# MEMS.net
KiCad netlist of a schematic drawn in Altium Designer
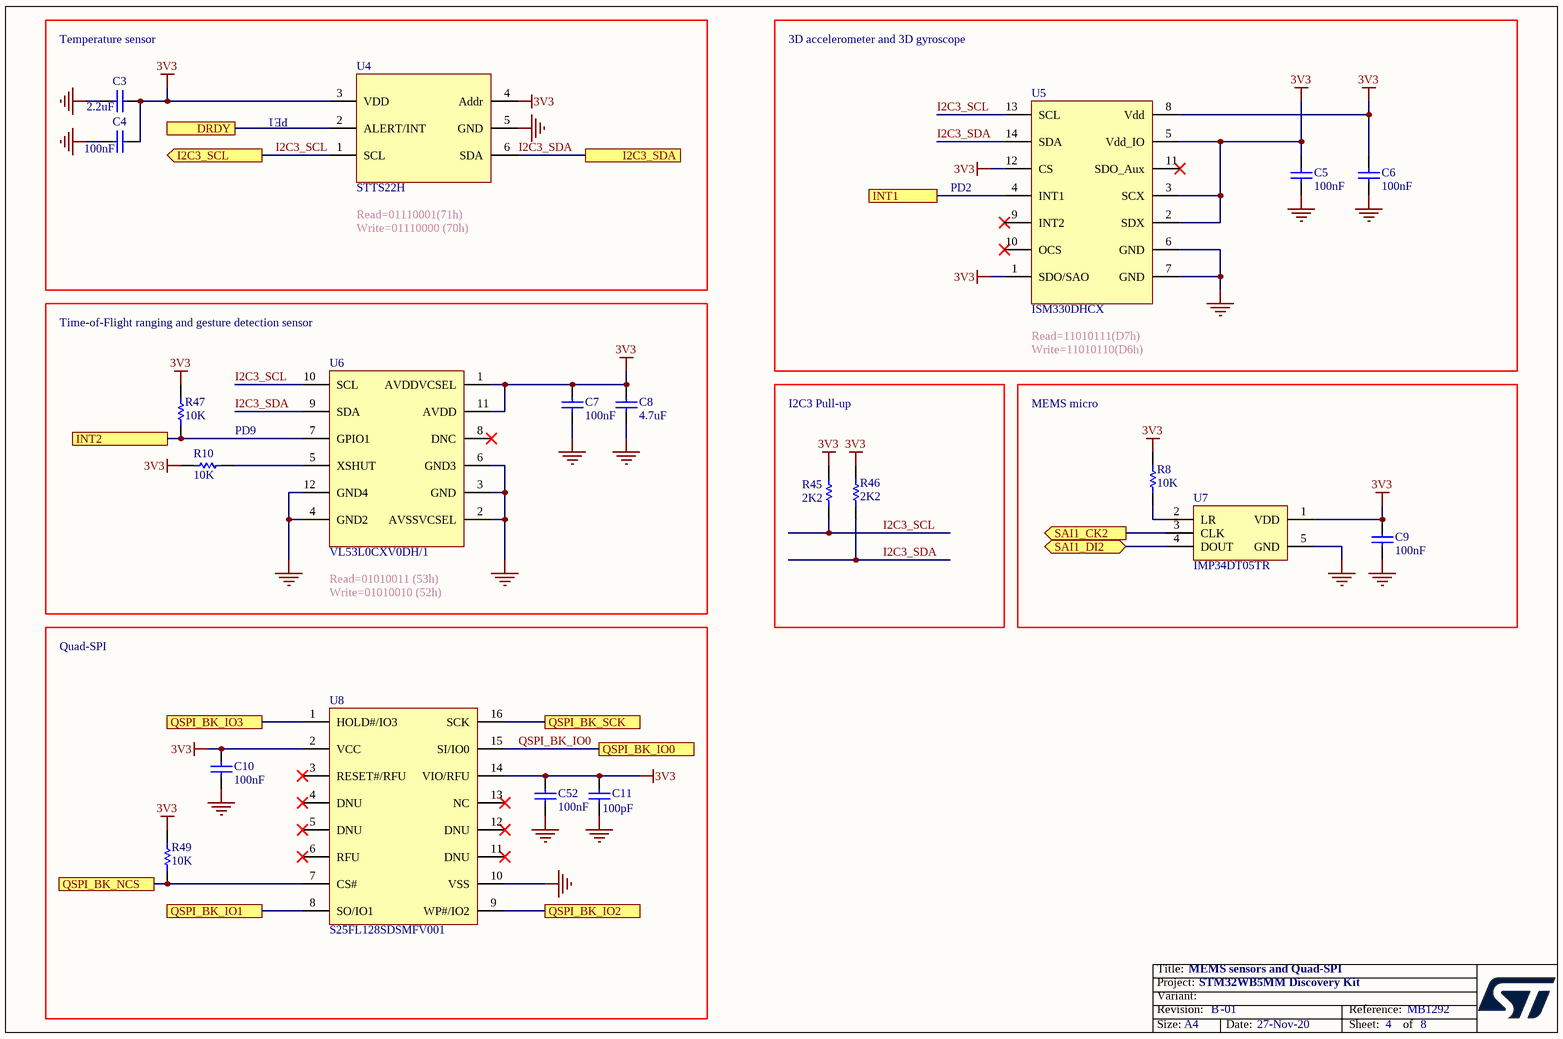
[diagram p0: MEMS.SchDoc]

(export (version "E")
  (design (tool "Eeschema 10.0.6"))
  (components
    (comp (ref "C3")
      (value "2.2uF")
      (footprint "C0603_H0P8")
      (description "Capacitor,MLCC, 2.2uF, 50V, X5R, +/-15%, 0603,T=0.8mm")
      (fields
        (field (name "INTERNAL_PART_NUMBER") "MCD-01540")
        (field (name "MANUFACTURER_PART_NUMBER") "GRM188R61H225KE11")
      )
      (libsource (lib "MCD_PARTS_database") (part "Capacitor"))
    )
    (comp (ref "C4")
      (value "100nF")
      (footprint "C0402")
      (description "Capacitor, MLCC, 100nF, 16V, X7R, +/-10%, 0402, T=0.5mm")
      (fields
        (field (name "INTERNAL_PART_NUMBER") "MCD-00006")
        (field (name "MANUFACTURER_PART_NUMBER") "CC0402KRX7R7BB104")
      )
      (libsource (lib "MCD_PARTS_database") (part "Capacitor"))
    )
    (comp (ref "C5")
      (value "100nF")
      (footprint "C0402")
      (description "Capacitor, MLCC, 100nF, 16V, X7R, +/-10%, 0402, T=0.5mm")
      (fields
        (field (name "INTERNAL_PART_NUMBER") "MCD-00006")
        (field (name "MANUFACTURER_PART_NUMBER") "CC0402KRX7R7BB104")
      )
      (libsource (lib "MCD_PARTS_database") (part "Capacitor"))
    )
    (comp (ref "C6")
      (value "100nF")
      (footprint "C0402")
      (description "Capacitor, MLCC, 100nF, 16V, X7R, +/-10%, 0402, T=0.5mm")
      (fields
        (field (name "INTERNAL_PART_NUMBER") "MCD-00006")
        (field (name "MANUFACTURER_PART_NUMBER") "CC0402KRX7R7BB104")
      )
      (libsource (lib "MCD_PARTS_database") (part "Capacitor"))
    )
    (comp (ref "C7")
      (value "100nF")
      (footprint "C0402")
      (description "Capacitor, MLCC, 100nF, 16V, X7R, +/-10%, 0402, T=0.5mm")
      (fields
        (field (name "INTERNAL_PART_NUMBER") "MCD-00006")
        (field (name "MANUFACTURER_PART_NUMBER") "CC0402KRX7R7BB104")
      )
      (libsource (lib "MCD_PARTS_database") (part "Capacitor"))
    )
    (comp (ref "C8")
      (value "4.7uF")
      (footprint "C0603")
      (description "Capacitor, MLCC, 4.7uF, 16V, X5R, +/-10%, 0603, T=0.8mm")
      (fields
        (field (name "INTERNAL_PART_NUMBER") "MCD-00009")
        (field (name "MANUFACTURER_PART_NUMBER") "CC0603KRX5R7BB475")
      )
      (libsource (lib "MCD_PARTS_database") (part "Capacitor"))
    )
    (comp (ref "C9")
      (value "100nF")
      (footprint "C0402")
      (description "Capacitor, MLCC, 100nF, 16V, X7R, +/-10%, 0402, T=0.5mm")
      (fields
        (field (name "INTERNAL_PART_NUMBER") "MCD-00006")
        (field (name "MANUFACTURER_PART_NUMBER") "CC0402KRX7R7BB104")
      )
      (libsource (lib "MCD_PARTS_database") (part "Capacitor"))
    )
    (comp (ref "C10")
      (value "100nF")
      (footprint "C0402")
      (description "Capacitor, MLCC, 100nF, 16V, X7R, +/-10%, 0402, T=0.5mm")
      (fields
        (field (name "INTERNAL_PART_NUMBER") "MCD-00006")
        (field (name "MANUFACTURER_PART_NUMBER") "CC0402KRX7R7BB104")
      )
      (libsource (lib "MCD_PARTS_database") (part "Capacitor"))
    )
    (comp (ref "C11")
      (value "100pF")
      (footprint "C0603_H0P8")
      (description "Capacitor,MLCC,100pF 50V,NPO,+/-5%, 0603,T=0,8mm")
      (fields
        (field (name "INTERNAL_PART_NUMBER") "MCD-01648")
        (field (name "MANUFACTURER_PART_NUMBER") "CC0603JRNPO9BN101")
      )
      (libsource (lib "MCD_PARTS_database") (part "Capacitor"))
    )
    (comp (ref "C52")
      (value "100nF")
      (footprint "C0402")
      (description "Capacitor, MLCC, 100nF, 16V, X7R, +/-10%, 0402, T=0.5mm")
      (fields
        (field (name "INTERNAL_PART_NUMBER") "MCD-00006")
        (field (name "MANUFACTURER_PART_NUMBER") "CC0402KRX7R7BB104")
      )
      (libsource (lib "MCD_PARTS_database") (part "Capacitor"))
    )
    (comp (ref "R8")
      (value "10K")
      (footprint "R0402")
      (description "Resistor,10K,0402,1%,1/16W")
      (fields
        (field (name "INTERNAL_PART_NUMBER") "MCD-00053")
        (field (name "MANUFACTURER_PART_NUMBER") "RC0402FR-0710KL")
      )
      (libsource (lib "MCD_PARTS_database") (part "Resistor"))
    )
    (comp (ref "R10")
      (value "10K")
      (footprint "R0402")
      (description "Resistor,10K,0402,1%,1/16W")
      (fields
        (field (name "INTERNAL_PART_NUMBER") "MCD-00053")
        (field (name "MANUFACTURER_PART_NUMBER") "RC0402FR-0710KL")
      )
      (libsource (lib "MCD_PARTS_database") (part "Resistor"))
    )
    (comp (ref "R45")
      (value "2K2")
      (footprint "R0603")
      (description "Resistor,2K2,0603,1%,1/10W")
      (fields (field (name "INTERNAL_PART_NUMBER") "MCD-00349") (field (name "MANUFACTURER") "YAGEO"))
      (libsource (lib "MCD_PARTS_database") (part "Resistor"))
    )
    (comp (ref "R46")
      (value "2K2")
      (footprint "R0603")
      (description "Resistor,2K2,0603,1%,1/10W")
      (fields (field (name "INTERNAL_PART_NUMBER") "MCD-00349") (field (name "MANUFACTURER") "YAGEO"))
      (libsource (lib "MCD_PARTS_database") (part "Resistor"))
    )
    (comp (ref "R47")
      (value "10K")
      (footprint "R0402")
      (description "Resistor,10K,0402,1%,1/16W")
      (fields
        (field (name "INTERNAL_PART_NUMBER") "MCD-00053")
        (field (name "MANUFACTURER_PART_NUMBER") "RC0402FR-0710KL")
      )
      (libsource (lib "MCD_PARTS_database") (part "Resistor"))
    )
    (comp (ref "R49")
      (value "10K")
      (footprint "R0402")
      (description "Resistor,10K,0402,1%,1/16W")
      (fields
        (field (name "INTERNAL_PART_NUMBER") "MCD-00053")
        (field (name "MANUFACTURER_PART_NUMBER") "RC0402FR-0710KL")
      )
      (libsource (lib "MCD_PARTS_database") (part "Resistor"))
    )
    (comp (ref "U4")
      (value "STTS22H")
      (footprint "ICC_UDFN6-EPAD_2X2_P065")
      (description "temperature sensor")
      (fields
        (field (name "INTERNAL_PART_NUMBER") "MCD-02159")
        (field (name "MANUFACTURER") "STMICROELECTRONICS")
      )
      (libsource (lib "MCD_PARTS_database") (part "STTS22H"))
    )
    (comp (ref "U5")
      (value "ISM330DHCX")
      (footprint "ICC_LGA14_3X2P5_P050")
      (fields
        (field (name "INTERNAL_PART_NUMBER") "MCD-02160")
        (field (name "MANUFACTURER_PART_NUMBER") "ISM330DHCXTR")
        (field (name "MANUFACTURER") "STMICROELECTRONICS")
      )
      (libsource (lib "MCD_PARTS_database") (part "ISM330DHCX"))
    )
    (comp (ref "U6")
      (value "VL53L0CXV0DH/1")
      (footprint "OPT_TOF_ST_VL53L0X_LGA12_4P4X2P4_P080")
      (description "Time-of-Flight ranging and gesture detection")
      (fields
        (field (name "INTERNAL_PART_NUMBER") "MCD-01730")
        (field (name "MANUFACTURER") "STMICROELECTRONICS")
      )
      (libsource (lib "MCD_PARTS_database") (part "VL53L0CXV0DH/1"))
    )
    (comp (ref "U7")
      (value "IMP34DT05TR")
      (footprint "MIC_HCLGA_3X4X1_4LD")
      (description "MEMS audio sensor omnidirectional digital microphone for industrial applications")
      (fields
        (field (name "INTERNAL_PART_NUMBER") "MCD-01715")
        (field (name "MANUFACTURER") "STMICROELECTRONICS")
      )
      (libsource (lib "MCD_PARTS_database") (part "IMP34DT05TR"))
    )
    (comp (ref "U8")
      (value "S25FL128SDSMFV001")
      (footprint "ICC_SOIC16_10P30X7P50_P127_H2P65")
      (description "Quad SPI with SOIC package 16-pins")
      (fields (field (name "INTERNAL_PART_NUMBER") "MCD-02038") (field (name "MANUFACTURER") "CYPRESS"))
      (libsource (lib "MCD_PARTS_database") (part "S25FL128SDSMFV001"))
    )
  )
  (nets
    (net (code "1") (name "/DRDY") (class "Default")
      (node (ref "U4") (pin "2") (pinfunction "ALERT/INT_2") (pintype "passive"))
    )
    (net (code "2") (name "/I2C3_SCL") (class "Default")
      (node (ref "R45") (pin "1") (pinfunction "1_1") (pintype "passive"))
      (node (ref "U4") (pin "1") (pinfunction "SCL_1") (pintype "passive"))
      (node (ref "U5") (pin "13") (pinfunction "SCL_13") (pintype "passive"))
      (node (ref "U6") (pin "10") (pinfunction "SCL_10") (pintype "passive"))
    )
    (net (code "3") (name "/I2C3_SDA") (class "Default")
      (node (ref "R46") (pin "1") (pinfunction "1_1") (pintype "passive"))
      (node (ref "U4") (pin "6") (pinfunction "SDA_6") (pintype "passive"))
      (node (ref "U5") (pin "14") (pinfunction "SDA_14") (pintype "passive"))
      (node (ref "U6") (pin "9") (pinfunction "SDA_9") (pintype "passive"))
    )
    (net (code "4") (name "/INT1") (class "Default")
      (node (ref "U5") (pin "4") (pinfunction "INT1_4") (pintype "passive"))
    )
    (net (code "5") (name "/INT2") (class "Default")
      (node (ref "R47") (pin "1") (pinfunction "1_1") (pintype "passive"))
      (node (ref "U6") (pin "7") (pinfunction "GPIO1_7") (pintype "passive"))
    )
    (net (code "6") (name "/QSPI_BK_IO0") (class "Default")
      (node (ref "U8") (pin "15") (pinfunction "SI/IO0_15") (pintype "passive"))
    )
    (net (code "7") (name "/QSPI_BK_IO1") (class "Default")
      (node (ref "U8") (pin "8") (pinfunction "SO/IO1_8") (pintype "passive"))
    )
    (net (code "8") (name "/QSPI_BK_IO2") (class "Default")
      (node (ref "U8") (pin "9") (pinfunction "WP#/IO2_9") (pintype "passive"))
    )
    (net (code "9") (name "/QSPI_BK_IO3") (class "Default")
      (node (ref "U8") (pin "1") (pinfunction "HOLD#/IO3_1") (pintype "passive"))
    )
    (net (code "10") (name "/QSPI_BK_NCS") (class "Default")
      (node (ref "R49") (pin "1") (pinfunction "1_1") (pintype "passive"))
      (node (ref "U8") (pin "7") (pinfunction "CS#_7") (pintype "passive"))
    )
    (net (code "11") (name "/QSPI_BK_SCK") (class "Default")
      (node (ref "U8") (pin "16") (pinfunction "SCK_16") (pintype "passive"))
    )
    (net (code "12") (name "/SAI1_CK2") (class "Default")
      (node (ref "U7") (pin "3") (pinfunction "CLK_3") (pintype "passive"))
    )
    (net (code "13") (name "/SAI1_DI2") (class "Default")
      (node (ref "U7") (pin "4") (pinfunction "DOUT_4") (pintype "passive"))
    )
    (net (code "14") (name "3V3") (class "Default")
      (node (ref "C10") (pin "2") (pinfunction "2_2") (pintype "passive"))
      (node (ref "C11") (pin "2") (pinfunction "2_2") (pintype "passive"))
      (node (ref "C3") (pin "2") (pinfunction "2_2") (pintype "passive"))
      (node (ref "C4") (pin "2") (pinfunction "2_2") (pintype "passive"))
      (node (ref "C5") (pin "2") (pinfunction "2_2") (pintype "passive"))
      (node (ref "C52") (pin "2") (pinfunction "2_2") (pintype "passive"))
      (node (ref "C6") (pin "2") (pinfunction "2_2") (pintype "passive"))
      (node (ref "C7") (pin "2") (pinfunction "2_2") (pintype "passive"))
      (node (ref "C8") (pin "2") (pinfunction "2_2") (pintype "passive"))
      (node (ref "C9") (pin "2") (pinfunction "2_2") (pintype "passive"))
      (node (ref "R10") (pin "1") (pinfunction "1_1") (pintype "passive"))
      (node (ref "R45") (pin "2") (pinfunction "2_2") (pintype "passive"))
      (node (ref "R46") (pin "2") (pinfunction "2_2") (pintype "passive"))
      (node (ref "R47") (pin "2") (pinfunction "2_2") (pintype "passive"))
      (node (ref "R49") (pin "2") (pinfunction "2_2") (pintype "passive"))
      (node (ref "R8") (pin "2") (pinfunction "2_2") (pintype "passive"))
      (node (ref "U4") (pin "3") (pinfunction "VDD_3") (pintype "passive"))
      (node (ref "U4") (pin "4") (pinfunction "Addr_4") (pintype "passive"))
      (node (ref "U5") (pin "1") (pinfunction "SDO/SAO_1") (pintype "passive"))
      (node (ref "U5") (pin "12") (pinfunction "CS_12") (pintype "passive"))
      (node (ref "U5") (pin "2") (pinfunction "SDX_2") (pintype "passive"))
      (node (ref "U5") (pin "3") (pinfunction "SCX_3") (pintype "passive"))
      (node (ref "U5") (pin "5") (pinfunction "Vdd_IO_5") (pintype "passive"))
      (node (ref "U5") (pin "8") (pinfunction "Vdd_8") (pintype "passive"))
      (node (ref "U6") (pin "1") (pinfunction "AVDDVCSEL_1") (pintype "passive"))
      (node (ref "U6") (pin "11") (pinfunction "AVDD_11") (pintype "passive"))
      (node (ref "U7") (pin "1") (pinfunction "VDD_1") (pintype "passive"))
      (node (ref "U8") (pin "14") (pinfunction "VIO/RFU_14") (pintype "passive"))
      (node (ref "U8") (pin "2") (pinfunction "VCC_2") (pintype "passive"))
    )
    (net (code "15") (name "GND") (class "Default")
      (node (ref "C10") (pin "1") (pinfunction "1_1") (pintype "passive"))
      (node (ref "C11") (pin "1") (pinfunction "1_1") (pintype "passive"))
      (node (ref "C3") (pin "1") (pinfunction "1_1") (pintype "passive"))
      (node (ref "C4") (pin "1") (pinfunction "1_1") (pintype "passive"))
      (node (ref "C5") (pin "1") (pinfunction "1_1") (pintype "passive"))
      (node (ref "C52") (pin "1") (pinfunction "1_1") (pintype "passive"))
      (node (ref "C6") (pin "1") (pinfunction "1_1") (pintype "passive"))
      (node (ref "C7") (pin "1") (pinfunction "1_1") (pintype "passive"))
      (node (ref "C8") (pin "1") (pinfunction "1_1") (pintype "passive"))
      (node (ref "C9") (pin "1") (pinfunction "1_1") (pintype "passive"))
      (node (ref "U4") (pin "5") (pinfunction "GND_5") (pintype "passive"))
      (node (ref "U5") (pin "6") (pinfunction "GND_6") (pintype "passive"))
      (node (ref "U5") (pin "7") (pinfunction "GND_7") (pintype "passive"))
      (node (ref "U6") (pin "12") (pinfunction "GND4_12") (pintype "passive"))
      (node (ref "U6") (pin "2") (pinfunction "AVSSVCSEL_2") (pintype "passive"))
      (node (ref "U6") (pin "3") (pinfunction "GND_3") (pintype "passive"))
      (node (ref "U6") (pin "4") (pinfunction "GND2_4") (pintype "passive"))
      (node (ref "U6") (pin "6") (pinfunction "GND3_6") (pintype "passive"))
      (node (ref "U7") (pin "5") (pinfunction "GND_5") (pintype "passive"))
      (node (ref "U8") (pin "10") (pinfunction "VSS_10") (pintype "passive"))
    )
    (net (code "16") (name "Net-(U6-XSHUT)") (class "Default")
      (node (ref "R10") (pin "2") (pinfunction "2_2") (pintype "passive"))
      (node (ref "U6") (pin "5") (pinfunction "XSHUT_5") (pintype "passive"))
    )
    (net (code "17") (name "Net-(U7-LR)") (class "Default")
      (node (ref "R8") (pin "1") (pinfunction "1_1") (pintype "passive"))
      (node (ref "U7") (pin "2") (pinfunction "LR_2") (pintype "passive"))
    )
    (net (code "18") (name "unconnected-(U5-INT2-Pad9)") (class "Default")
      (node (ref "U5") (pin "9") (pinfunction "INT2_9") (pintype "passive+no_connect"))
    )
    (net (code "19") (name "unconnected-(U5-OCS-Pad10)") (class "Default")
      (node (ref "U5") (pin "10") (pinfunction "OCS_10") (pintype "passive+no_connect"))
    )
    (net (code "20") (name "unconnected-(U5-SDO_Aux-Pad11)") (class "Default")
      (node (ref "U5") (pin "11") (pinfunction "SDO_Aux_11") (pintype "passive+no_connect"))
    )
    (net (code "21") (name "unconnected-(U6-DNC-Pad8)") (class "Default")
      (node (ref "U6") (pin "8") (pinfunction "DNC_8") (pintype "passive+no_connect"))
    )
    (net (code "22") (name "unconnected-(U8-DNU-Pad4)") (class "Default")
      (node (ref "U8") (pin "4") (pinfunction "DNU_4") (pintype "passive+no_connect"))
    )
    (net (code "23") (name "unconnected-(U8-DNU-Pad5)") (class "Default")
      (node (ref "U8") (pin "5") (pinfunction "DNU_5") (pintype "passive+no_connect"))
    )
    (net (code "24") (name "unconnected-(U8-DNU-Pad11)") (class "Default")
      (node (ref "U8") (pin "11") (pinfunction "DNU_11") (pintype "passive+no_connect"))
    )
    (net (code "25") (name "unconnected-(U8-DNU-Pad12)") (class "Default")
      (node (ref "U8") (pin "12") (pinfunction "DNU_12") (pintype "passive+no_connect"))
    )
    (net (code "26") (name "unconnected-(U8-NC-Pad13)") (class "Default")
      (node (ref "U8") (pin "13") (pinfunction "NC_13") (pintype "passive+no_connect"))
    )
    (net (code "27") (name "unconnected-(U8-RESET#{slash}RFU-Pad3)") (class "Default")
      (node (ref "U8") (pin "3") (pinfunction "RESET#/RFU_3") (pintype "passive+no_connect"))
    )
    (net (code "28") (name "unconnected-(U8-RFU-Pad6)") (class "Default")
      (node (ref "U8") (pin "6") (pinfunction "RFU_6") (pintype "passive+no_connect"))
    )
  )
)
